# JLink_MCU_flash_cable.net
KiCad netlist of a schematic drawn in EAGLE
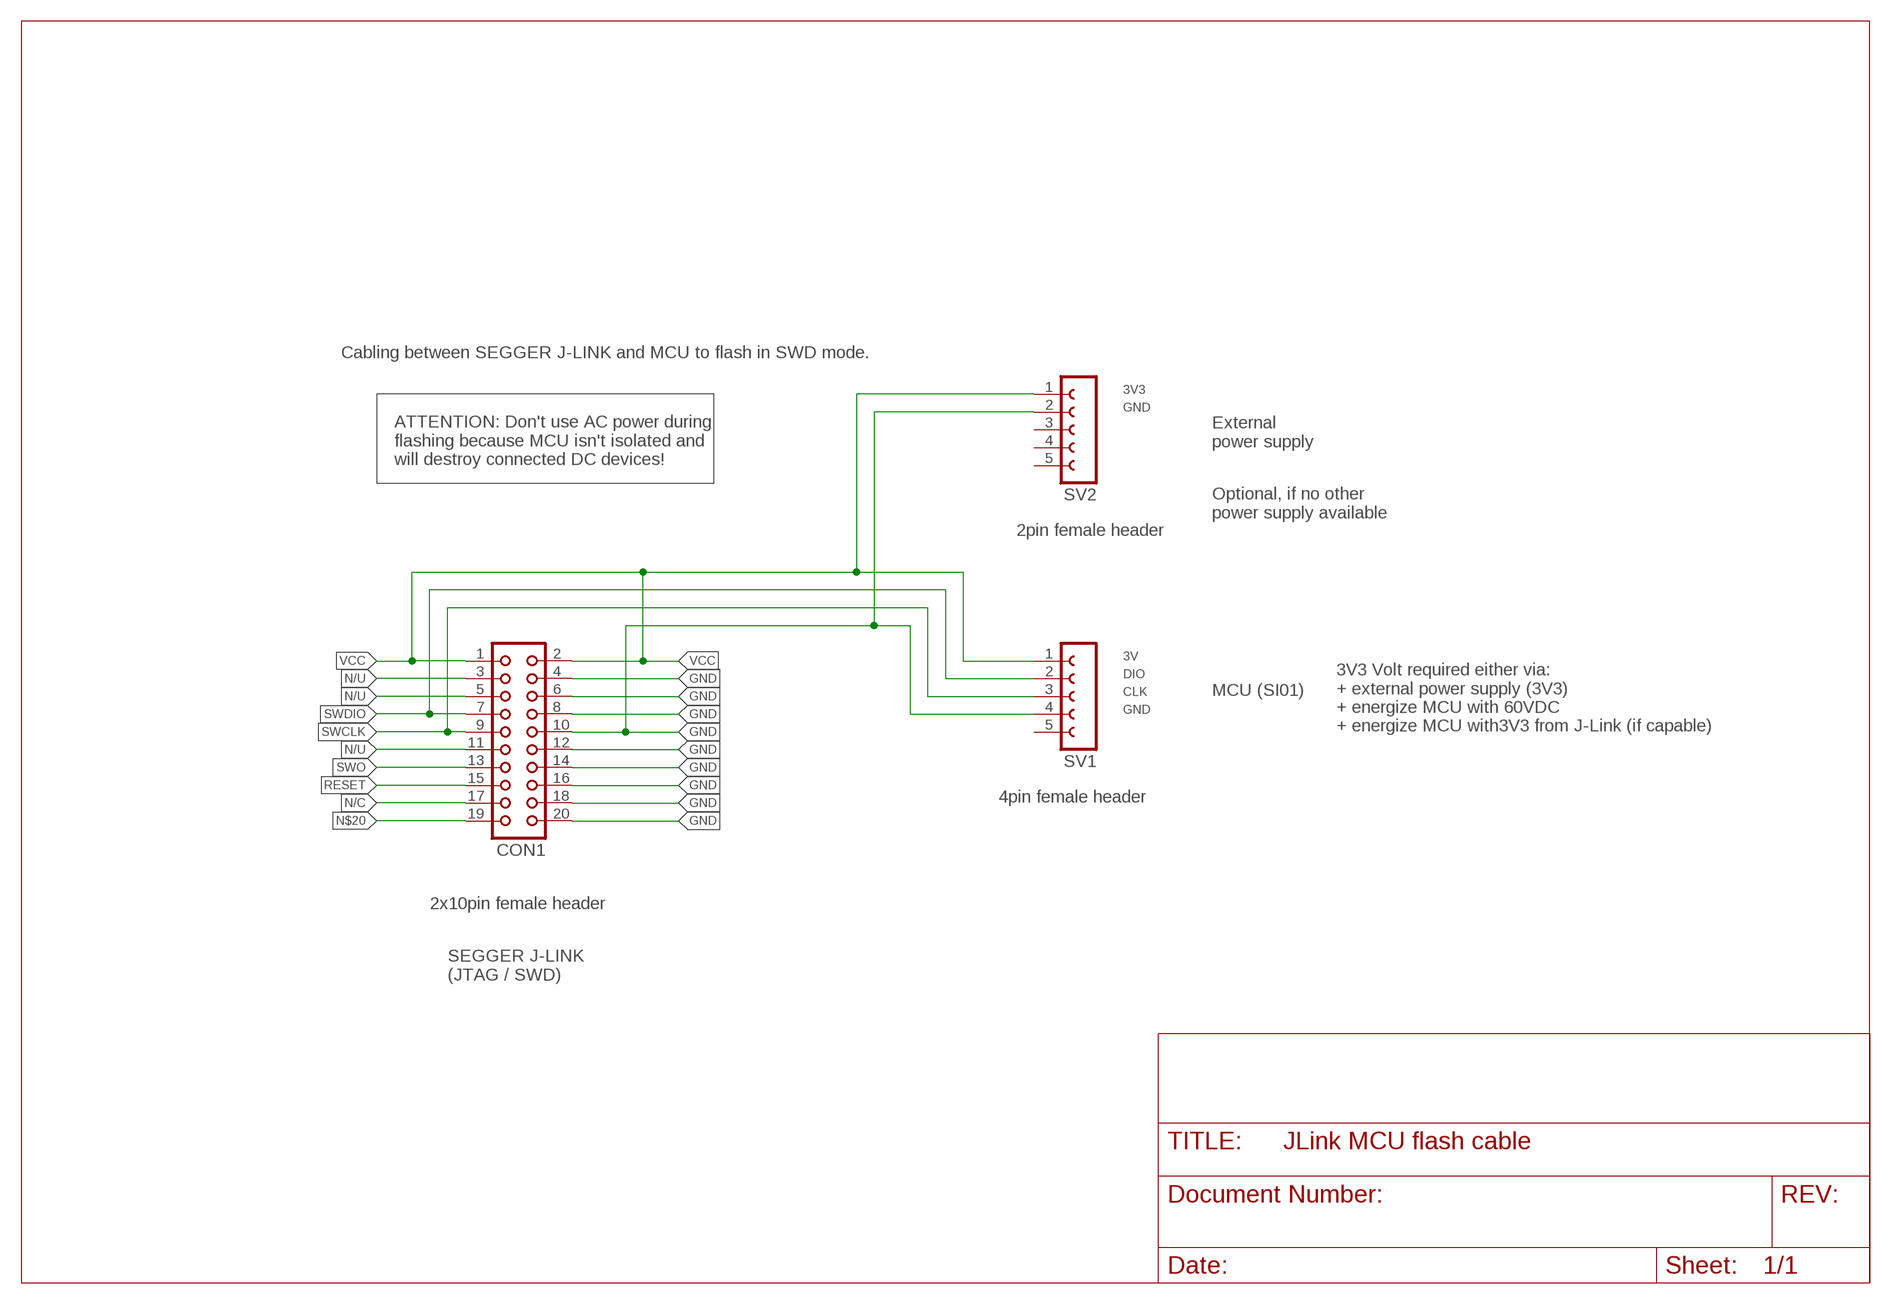
[diagram p0: schematic, sheet 1]

(export (version "E")
  (design (tool "Eeschema 10.0.6"))
  (components
    (comp (ref "CON1")
      (value "CON20")
      (footprint "eagle-import:CON20")
      (libsource (lib "eagle-import") (part "CON20"))
    )
    (comp (ref "SV1")
      (value "FE05-1")
      (footprint "eagle-import:FE05-1")
      (libsource (lib "eagle-import") (part "FE05-1"))
    )
    (comp (ref "SV2")
      (value "FE05-1")
      (footprint "eagle-import:FE05-1")
      (libsource (lib "eagle-import") (part "FE05-1"))
    )
  )
  (nets
    (net (code "1") (name "GND") (class "Default")
      (node (ref "CON1") (pin "10") (pinfunction "10_10") (pintype "passive"))
      (node (ref "CON1") (pin "12") (pinfunction "12_12") (pintype "passive"))
      (node (ref "CON1") (pin "14") (pinfunction "14_14") (pintype "passive"))
      (node (ref "CON1") (pin "16") (pinfunction "16_16") (pintype "passive"))
      (node (ref "CON1") (pin "18") (pinfunction "18_18") (pintype "passive"))
      (node (ref "CON1") (pin "20") (pinfunction "20_20") (pintype "passive"))
      (node (ref "CON1") (pin "4") (pinfunction "4_4") (pintype "passive"))
      (node (ref "CON1") (pin "6") (pinfunction "6_6") (pintype "passive"))
      (node (ref "CON1") (pin "8") (pinfunction "8_8") (pintype "passive"))
      (node (ref "SV1") (pin "4") (pinfunction "4_4") (pintype "passive"))
      (node (ref "SV2") (pin "2") (pinfunction "2_2") (pintype "passive"))
    )
    (net (code "2") (name "N$20") (class "Default")
      (node (ref "CON1") (pin "19") (pinfunction "19_19") (pintype "passive"))
    )
    (net (code "3") (name "N{slash}C") (class "Default")
      (node (ref "CON1") (pin "17") (pinfunction "17_17") (pintype "passive"))
    )
    (net (code "4") (name "N{slash}U") (class "Default")
      (node (ref "CON1") (pin "11") (pinfunction "11_11") (pintype "passive"))
      (node (ref "CON1") (pin "3") (pinfunction "3_3") (pintype "passive"))
      (node (ref "CON1") (pin "5") (pinfunction "5_5") (pintype "passive"))
    )
    (net (code "5") (name "RESET") (class "Default")
      (node (ref "CON1") (pin "15") (pinfunction "15_15") (pintype "passive"))
    )
    (net (code "6") (name "SWCLK") (class "Default")
      (node (ref "CON1") (pin "9") (pinfunction "9_9") (pintype "passive"))
      (node (ref "SV1") (pin "3") (pinfunction "3_3") (pintype "passive"))
    )
    (net (code "7") (name "SWDIO") (class "Default")
      (node (ref "CON1") (pin "7") (pinfunction "7_7") (pintype "passive"))
      (node (ref "SV1") (pin "2") (pinfunction "2_2") (pintype "passive"))
    )
    (net (code "8") (name "SWO") (class "Default")
      (node (ref "CON1") (pin "13") (pinfunction "13_13") (pintype "passive"))
    )
    (net (code "9") (name "VCC") (class "Default")
      (node (ref "CON1") (pin "1") (pinfunction "1_1") (pintype "passive"))
      (node (ref "CON1") (pin "2") (pinfunction "2_2") (pintype "passive"))
      (node (ref "SV1") (pin "1") (pinfunction "1_1") (pintype "passive"))
      (node (ref "SV2") (pin "1") (pinfunction "1_1") (pintype "passive"))
    )
    (net (code "10") (name "unconnected-(SV1-Pad5)") (class "Default")
      (node (ref "SV1") (pin "5") (pinfunction "5_5") (pintype "passive"))
    )
    (net (code "11") (name "unconnected-(SV2-Pad3)") (class "Default")
      (node (ref "SV2") (pin "3") (pinfunction "3_3") (pintype "passive"))
    )
    (net (code "12") (name "unconnected-(SV2-Pad4)") (class "Default")
      (node (ref "SV2") (pin "4") (pinfunction "4_4") (pintype "passive"))
    )
    (net (code "13") (name "unconnected-(SV2-Pad5)") (class "Default")
      (node (ref "SV2") (pin "5") (pinfunction "5_5") (pintype "passive"))
    )
  )
)
